# Transmitter_ks0108_version.net
KiCad netlist of a schematic drawn in EAGLE
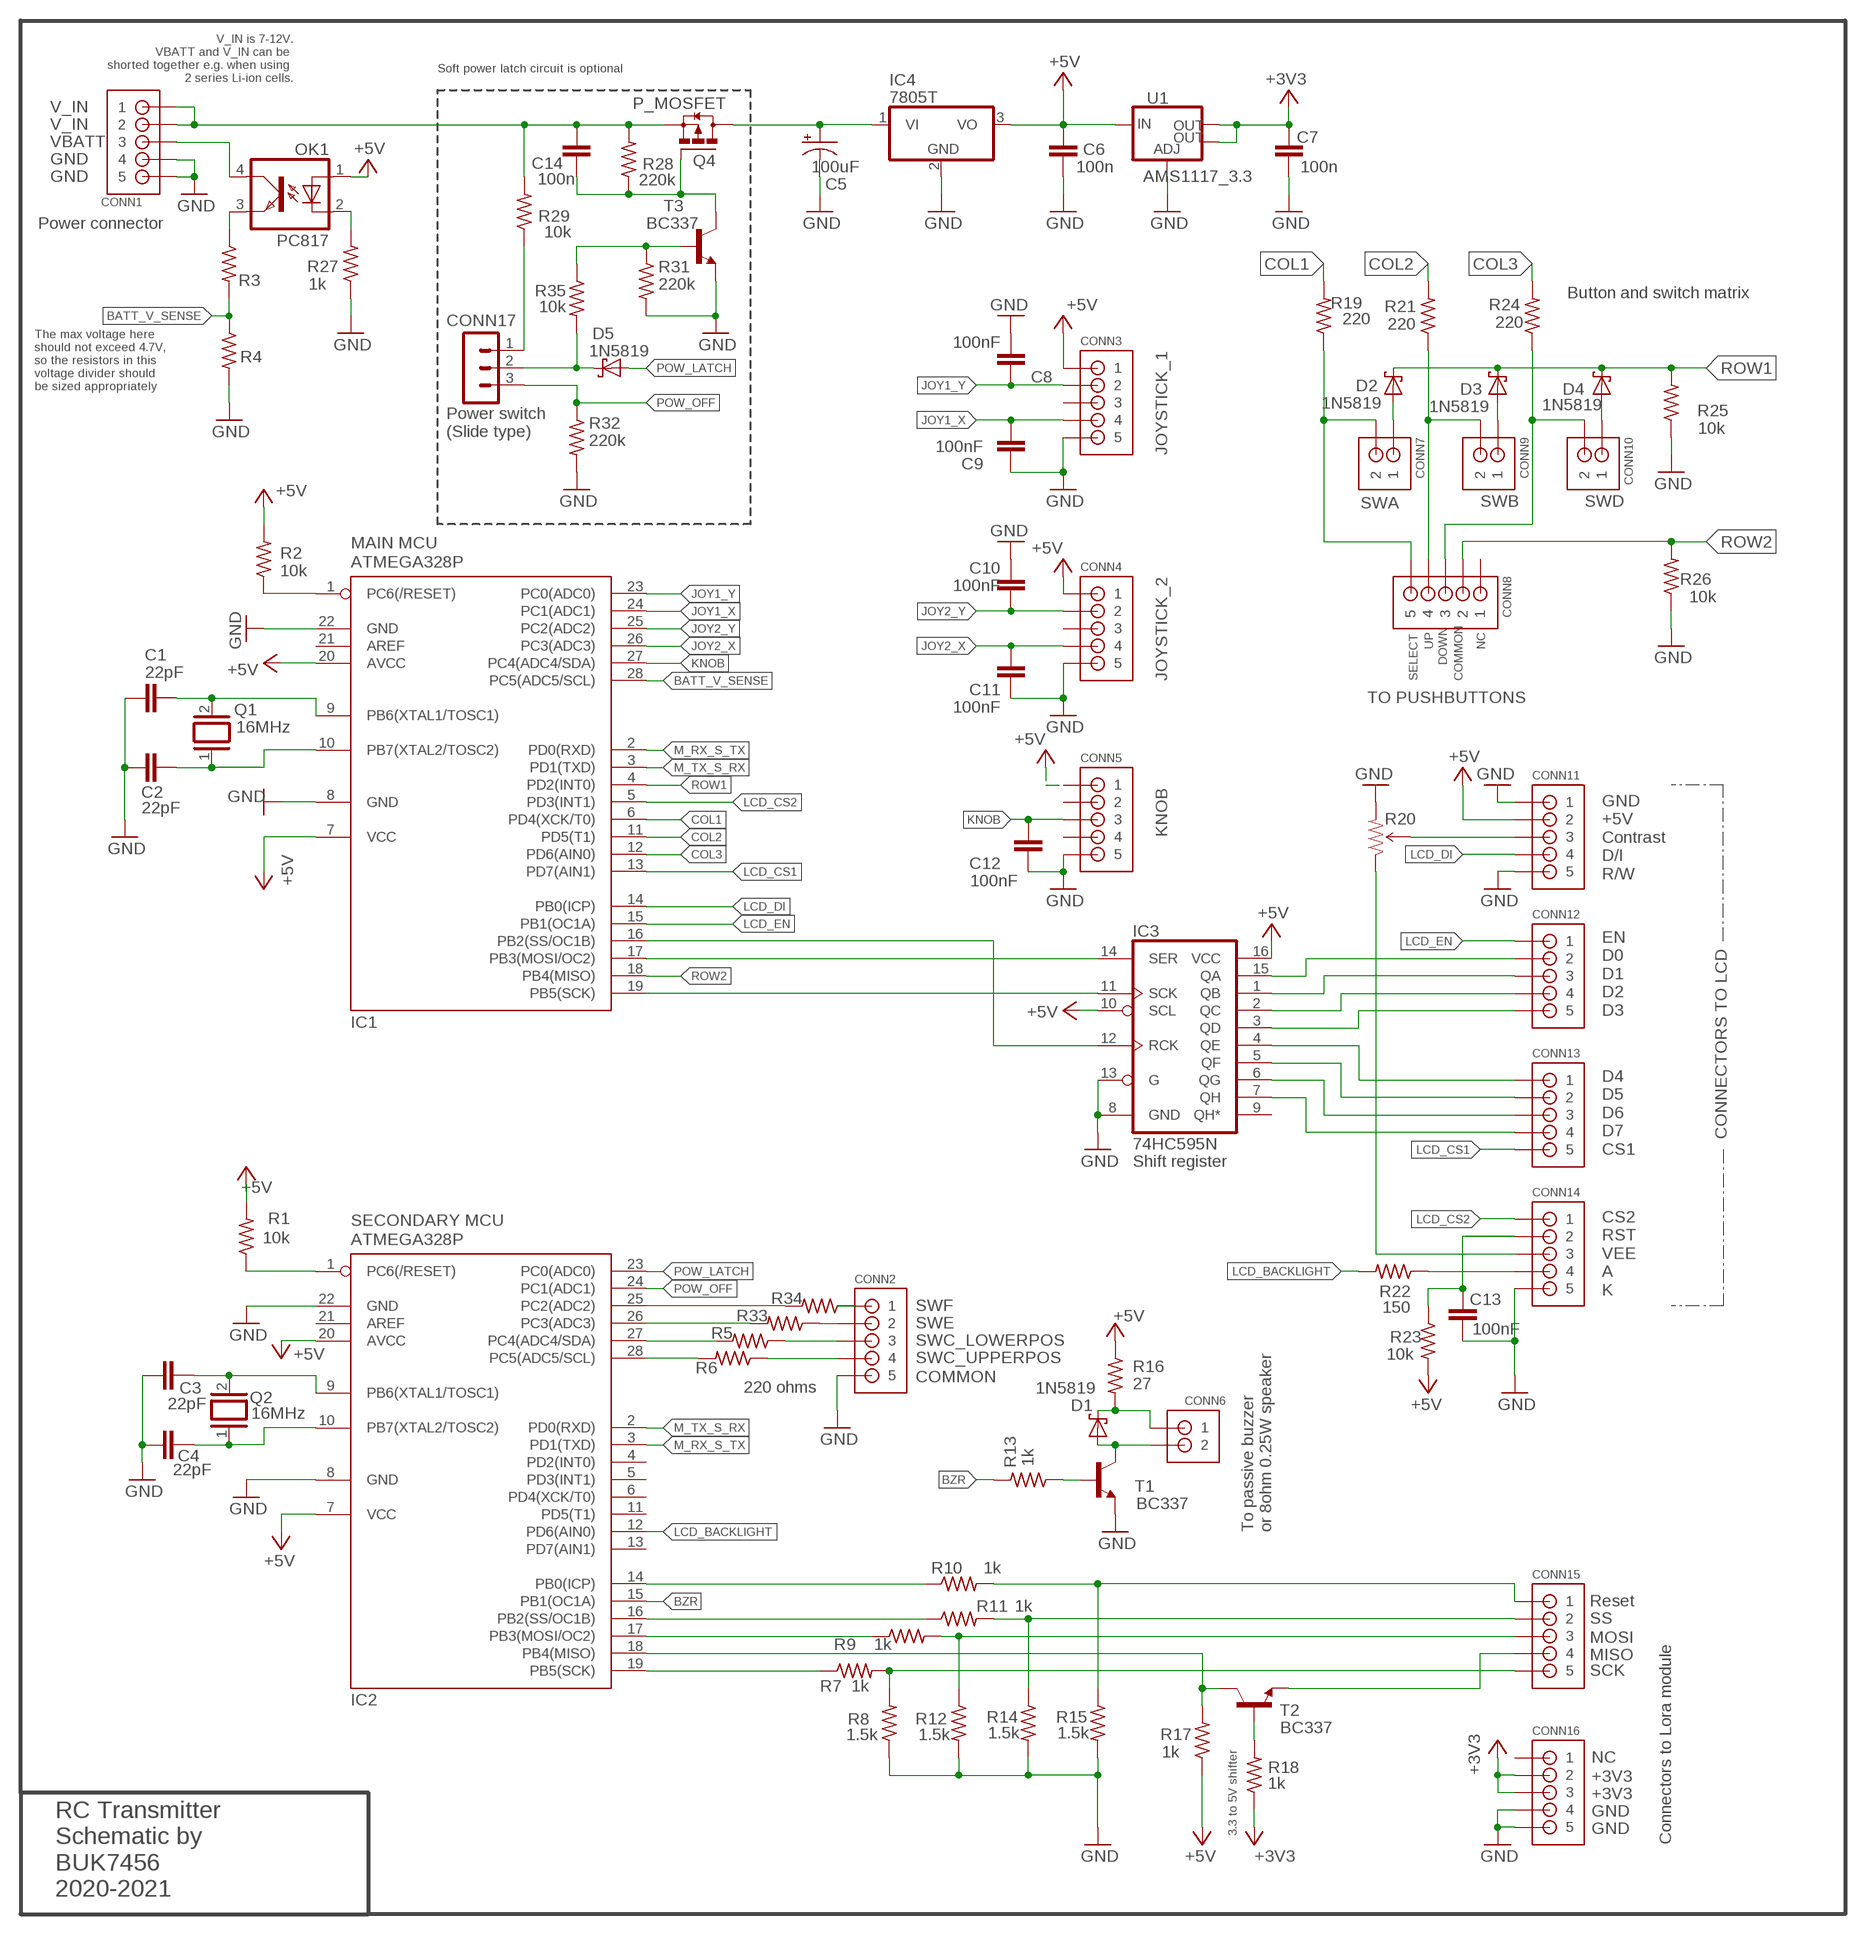
[diagram p0: schematic, sheet 1]

(export (version "E")
  (design (tool "Eeschema 10.0.6"))
  (components
    (comp (ref "C1")
      (value "22pF")
      (footprint "eagle-import:C025-025X050")
      (libsource (lib "eagle-import") (part "C-EU025-025X050"))
    )
    (comp (ref "C2")
      (value "22pF")
      (footprint "eagle-import:C025-025X050")
      (libsource (lib "eagle-import") (part "C-EU025-025X050"))
    )
    (comp (ref "C3")
      (value "22pF")
      (footprint "eagle-import:C025-025X050")
      (libsource (lib "eagle-import") (part "C-EU025-025X050"))
    )
    (comp (ref "C4")
      (value "22pF")
      (footprint "eagle-import:C025-025X050")
      (libsource (lib "eagle-import") (part "C-EU025-025X050"))
    )
    (comp (ref "C5")
      (value "100uF")
      (footprint "eagle-import:E2,5-6E")
      (libsource (lib "eagle-import") (part "CPOL-USE2,5-6E"))
    )
    (comp (ref "C6")
      (value "100n")
      (footprint "eagle-import:C025-025X050")
      (libsource (lib "eagle-import") (part "C-EU025-025X050"))
    )
    (comp (ref "C7")
      (value "100n")
      (footprint "eagle-import:C025-025X050")
      (libsource (lib "eagle-import") (part "C-EU025-025X050"))
    )
    (comp (ref "C8")
      (value "100nF")
      (footprint "eagle-import:C025-025X050")
      (libsource (lib "eagle-import") (part "C-EU025-025X050"))
    )
    (comp (ref "C9")
      (value "100nF")
      (footprint "eagle-import:C025-025X050")
      (libsource (lib "eagle-import") (part "C-EU025-025X050"))
    )
    (comp (ref "C10")
      (value "100nF")
      (footprint "eagle-import:C025-025X050")
      (libsource (lib "eagle-import") (part "C-EU025-025X050"))
    )
    (comp (ref "C11")
      (value "100nF")
      (footprint "eagle-import:C025-025X050")
      (libsource (lib "eagle-import") (part "C-EU025-025X050"))
    )
    (comp (ref "C12")
      (value "100nF")
      (footprint "eagle-import:C025-025X050")
      (libsource (lib "eagle-import") (part "C-EU025-025X050"))
    )
    (comp (ref "C13")
      (value "100nF")
      (footprint "eagle-import:C025-025X050")
      (libsource (lib "eagle-import") (part "C-EU025-025X050"))
    )
    (comp (ref "C14")
      (value "100n")
      (footprint "eagle-import:C025-025X050")
      (libsource (lib "eagle-import") (part "C-EU025-025X050"))
    )
    (comp (ref "CONN1")
      (value "POW")
      (footprint "eagle-import:JST_B5B-PH_HEADER")
      (libsource (lib "eagle-import") (part "JST-PH_5-PIN_HEADER"))
    )
    (comp (ref "CONN2")
      (value "RADIO")
      (footprint "eagle-import:JST_B5B-PH_HEADER")
      (libsource (lib "eagle-import") (part "JST-PH_5-PIN_HEADER"))
    )
    (comp (ref "CONN3")
      (value "JST-PH_5-PIN_HEADER")
      (footprint "eagle-import:JST_B5B-PH_HEADER")
      (libsource (lib "eagle-import") (part "JST-PH_5-PIN_HEADER"))
    )
    (comp (ref "CONN4")
      (value "JST-PH_5-PIN_HEADER")
      (footprint "eagle-import:JST_B5B-PH_HEADER")
      (libsource (lib "eagle-import") (part "JST-PH_5-PIN_HEADER"))
    )
    (comp (ref "CONN5")
      (value "JST-PH_5-PIN_HEADER")
      (footprint "eagle-import:JST_B5B-PH_HEADER")
      (libsource (lib "eagle-import") (part "JST-PH_5-PIN_HEADER"))
    )
    (comp (ref "CONN6")
      (value "JST-PH_2-PIN_HEADER")
      (footprint "eagle-import:JST_B2B-PH_HEADER")
      (libsource (lib "eagle-import") (part "JST-PH_2-PIN_HEADER"))
    )
    (comp (ref "CONN7")
      (value "JST-PH_2-PIN_HEADER")
      (footprint "eagle-import:JST_B2B-PH_HEADER")
      (libsource (lib "eagle-import") (part "JST-PH_2-PIN_HEADER"))
    )
    (comp (ref "CONN8")
      (value "JST-PH_5-PIN_HEADER")
      (footprint "eagle-import:JST_B5B-PH_HEADER")
      (libsource (lib "eagle-import") (part "JST-PH_5-PIN_HEADER"))
    )
    (comp (ref "CONN9")
      (value "JST-PH_2-PIN_HEADER")
      (footprint "eagle-import:JST_B2B-PH_HEADER")
      (libsource (lib "eagle-import") (part "JST-PH_2-PIN_HEADER"))
    )
    (comp (ref "CONN10")
      (value "JST-PH_2-PIN_HEADER")
      (footprint "eagle-import:JST_B2B-PH_HEADER")
      (libsource (lib "eagle-import") (part "JST-PH_2-PIN_HEADER"))
    )
    (comp (ref "CONN11")
      (value "AUX")
      (footprint "eagle-import:JST_B5B-PH_HEADER")
      (libsource (lib "eagle-import") (part "JST-PH_5-PIN_HEADER"))
    )
    (comp (ref "CONN12")
      (value "AUX")
      (footprint "eagle-import:JST_B5B-PH_HEADER")
      (libsource (lib "eagle-import") (part "JST-PH_5-PIN_HEADER"))
    )
    (comp (ref "CONN13")
      (value "AUX")
      (footprint "eagle-import:JST_B5B-PH_HEADER")
      (libsource (lib "eagle-import") (part "JST-PH_5-PIN_HEADER"))
    )
    (comp (ref "CONN14")
      (value "AUX")
      (footprint "eagle-import:JST_B5B-PH_HEADER")
      (libsource (lib "eagle-import") (part "JST-PH_5-PIN_HEADER"))
    )
    (comp (ref "CONN15")
      (value "JST-PH_5-PIN_HEADER")
      (footprint "eagle-import:JST_B5B-PH_HEADER")
      (libsource (lib "eagle-import") (part "JST-PH_5-PIN_HEADER"))
    )
    (comp (ref "CONN16")
      (value "JST-PH_5-PIN_HEADER")
      (footprint "eagle-import:JST_B5B-PH_HEADER")
      (libsource (lib "eagle-import") (part "JST-PH_5-PIN_HEADER"))
    )
    (comp (ref "CONN17")
      (value "MA03-1")
      (footprint "eagle-import:MA03-1")
      (libsource (lib "eagle-import") (part "MA03-1"))
    )
    (comp (ref "D1")
      (value "1N5819")
      (footprint "eagle-import:DO41-7.6")
      (libsource (lib "eagle-import") (part "1N5817-B"))
    )
    (comp (ref "D2")
      (value "1N5819")
      (footprint "eagle-import:DO41-7.6")
      (libsource (lib "eagle-import") (part "1N5817-B"))
    )
    (comp (ref "D3")
      (value "1N5819")
      (footprint "eagle-import:DO41-7.6")
      (libsource (lib "eagle-import") (part "1N5817-B"))
    )
    (comp (ref "D4")
      (value "1N5819")
      (footprint "eagle-import:DO41-7.6")
      (libsource (lib "eagle-import") (part "1N5817-B"))
    )
    (comp (ref "D5")
      (value "1N5819")
      (footprint "eagle-import:DO41-7.6")
      (libsource (lib "eagle-import") (part "1N5817-B"))
    )
    (comp (ref "IC1")
      (value "ATMEGA328P")
      (footprint "eagle-import:DIL28-3")
      (libsource (lib "eagle-import") (part "MEGA8-P"))
    )
    (comp (ref "IC2")
      (value "ATMEGA328P")
      (footprint "eagle-import:DIL28-3")
      (libsource (lib "eagle-import") (part "MEGA8-P"))
    )
    (comp (ref "IC3")
      (value "74HC595N")
      (footprint "eagle-import:DIL16")
      (libsource (lib "eagle-import") (part "74595NLS"))
    )
    (comp (ref "IC4")
      (value "7805T")
      (footprint "eagle-import:TO220H")
      (libsource (lib "eagle-import") (part "78T05"))
    )
    (comp (ref "OK1")
      (value "PC817")
      (footprint "eagle-import:DIL04")
      (fields (field (name "MPN") "PC817X4J000F"))
      (libsource (lib "eagle-import") (part "PC817"))
    )
    (comp (ref "Q1")
      (value "16MHz")
      (footprint "eagle-import:QS")
      (libsource (lib "eagle-import") (part "XTAL/S"))
    )
    (comp (ref "Q2")
      (value "16MHz")
      (footprint "eagle-import:QS")
      (libsource (lib "eagle-import") (part "XTAL/S"))
    )
    (comp (ref "Q4")
      (value "P_MOSFET")
      (footprint "eagle-import:SUPER-SOT3")
      (libsource (lib "eagle-import") (part "FDN360P"))
    )
    (comp (ref "R1")
      (value "10k")
      (footprint "eagle-import:0204_5")
      (libsource (lib "eagle-import") (part "R-US_0204/5"))
    )
    (comp (ref "R2")
      (value "10k")
      (footprint "eagle-import:0207_10")
      (libsource (lib "eagle-import") (part "R-US_0207/10"))
    )
    (comp (ref "R3")
      (value "1k")
      (footprint "eagle-import:0207_10")
      (libsource (lib "eagle-import") (part "R-US_0207/10"))
    )
    (comp (ref "R4")
      (value "1k")
      (footprint "eagle-import:0204V")
      (libsource (lib "eagle-import") (part "resistor_R-US_0204/2V"))
    )
    (comp (ref "R5")
      (value "220")
      (footprint "eagle-import:0204_7")
      (libsource (lib "eagle-import") (part "R-US_0204/7"))
    )
    (comp (ref "R6")
      (value "220")
      (footprint "eagle-import:0204_7")
      (libsource (lib "eagle-import") (part "R-US_0204/7"))
    )
    (comp (ref "R7")
      (value "1k")
      (footprint "eagle-import:0204_5")
      (libsource (lib "eagle-import") (part "R-US_0204/5"))
    )
    (comp (ref "R8")
      (value "1.5k")
      (footprint "eagle-import:0204V")
      (libsource (lib "eagle-import") (part "R-US_0204/2V"))
    )
    (comp (ref "R9")
      (value "1k")
      (footprint "eagle-import:0204_5")
      (libsource (lib "eagle-import") (part "R-US_0204/5"))
    )
    (comp (ref "R10")
      (value "1k")
      (footprint "eagle-import:0204_5")
      (libsource (lib "eagle-import") (part "R-US_0204/5"))
    )
    (comp (ref "R11")
      (value "1k")
      (footprint "eagle-import:0204_5")
      (libsource (lib "eagle-import") (part "R-US_0204/5"))
    )
    (comp (ref "R12")
      (value "1.5k")
      (footprint "eagle-import:0204V")
      (libsource (lib "eagle-import") (part "R-US_0204/2V"))
    )
    (comp (ref "R13")
      (value "1k")
      (footprint "eagle-import:0204_5")
      (libsource (lib "eagle-import") (part "R-US_0204/5"))
    )
    (comp (ref "R14")
      (value "1.5k")
      (footprint "eagle-import:0204V")
      (libsource (lib "eagle-import") (part "R-US_0204/2V"))
    )
    (comp (ref "R15")
      (value "1.5k")
      (footprint "eagle-import:0204V")
      (libsource (lib "eagle-import") (part "R-US_0204/2V"))
    )
    (comp (ref "R16")
      (value "27")
      (footprint "eagle-import:0204_7")
      (libsource (lib "eagle-import") (part "R-US_0204/7"))
    )
    (comp (ref "R17")
      (value "1k")
      (footprint "eagle-import:0204_7")
      (libsource (lib "eagle-import") (part "R-US_0204/7"))
    )
    (comp (ref "R18")
      (value "1k")
      (footprint "eagle-import:0204_5")
      (libsource (lib "eagle-import") (part "R-US_0204/5"))
    )
    (comp (ref "R19")
      (value "220")
      (footprint "eagle-import:0204_7")
      (libsource (lib "eagle-import") (part "R-US_0204/7"))
    )
    (comp (ref "R20")
      (value "TRIMPOTPTH")
      (footprint "eagle-import:TRIM_POT_PTH")
      (libsource (lib "eagle-import") (part "TRIMPOTPTH"))
    )
    (comp (ref "R21")
      (value "220")
      (footprint "eagle-import:0207_10")
      (libsource (lib "eagle-import") (part "R-US_0207/10"))
    )
    (comp (ref "R22")
      (value "150")
      (footprint "eagle-import:0204V")
      (libsource (lib "eagle-import") (part "R-US_0204/2V"))
    )
    (comp (ref "R23")
      (value "10k")
      (footprint "eagle-import:0204_5")
      (libsource (lib "eagle-import") (part "resistor_R-US_0204/5"))
    )
    (comp (ref "R24")
      (value "220")
      (footprint "eagle-import:0204_7")
      (libsource (lib "eagle-import") (part "R-US_0204/7"))
    )
    (comp (ref "R25")
      (value "10k")
      (footprint "eagle-import:0204V")
      (libsource (lib "eagle-import") (part "R-US_0204/2V"))
    )
    (comp (ref "R26")
      (value "10k")
      (footprint "eagle-import:0204V")
      (libsource (lib "eagle-import") (part "R-US_0204/2V"))
    )
    (comp (ref "R27")
      (value "1k")
      (footprint "eagle-import:0204V")
      (libsource (lib "eagle-import") (part "R-US_0204/2V"))
    )
    (comp (ref "R28")
      (value "220k")
      (footprint "eagle-import:0204_7")
      (libsource (lib "eagle-import") (part "R-US_0204/7"))
    )
    (comp (ref "R29")
      (value "10k")
      (footprint "eagle-import:0204_7")
      (libsource (lib "eagle-import") (part "R-US_0204/7"))
    )
    (comp (ref "R31")
      (value "220k")
      (footprint "eagle-import:0204_7")
      (libsource (lib "eagle-import") (part "R-US_0204/7"))
    )
    (comp (ref "R32")
      (value "220k")
      (footprint "eagle-import:0204_7")
      (libsource (lib "eagle-import") (part "R-US_0204/7"))
    )
    (comp (ref "R33")
      (value "220")
      (footprint "eagle-import:0204_7")
      (libsource (lib "eagle-import") (part "R-US_0204/7"))
    )
    (comp (ref "R34")
      (value "220")
      (footprint "eagle-import:0204_7")
      (libsource (lib "eagle-import") (part "R-US_0204/7"))
    )
    (comp (ref "R35")
      (value "10k")
      (footprint "eagle-import:0204_7")
      (libsource (lib "eagle-import") (part "R-US_0204/7"))
    )
    (comp (ref "T1")
      (value "BC337")
      (footprint "eagle-import:TO92")
      (libsource (lib "eagle-import") (part "BC337"))
    )
    (comp (ref "T2")
      (value "BC337")
      (footprint "eagle-import:TO92")
      (libsource (lib "eagle-import") (part "BC337"))
    )
    (comp (ref "T3")
      (value "BC337")
      (footprint "eagle-import:TO92")
      (libsource (lib "eagle-import") (part "BC337"))
    )
    (comp (ref "U1")
      (value "AMS1117_3.3")
      (footprint "eagle-import:SOT223")
      (libsource (lib "eagle-import") (part "V_REG_LM1117SOT223"))
    )
  )
  (nets
    (net (code "1") (name "+3V3") (class "Default")
      (node (ref "C7") (pin "2") (pinfunction "2_2") (pintype "passive"))
      (node (ref "CONN16") (pin "P2") (pinfunction "2_P2") (pintype "bidirectional"))
      (node (ref "CONN16") (pin "P3") (pinfunction "3_P3") (pintype "bidirectional"))
      (node (ref "R18") (pin "1") (pinfunction "1_1") (pintype "passive"))
      (node (ref "U1") (pin "2") (pinfunction "OUT_2") (pintype "output"))
      (node (ref "U1") (pin "4") (pinfunction "OUT_4") (pintype "output"))
    )
    (net (code "2") (name "+5V") (class "Default")
      (node (ref "C6") (pin "2") (pinfunction "2_2") (pintype "passive"))
      (node (ref "CONN11") (pin "P2") (pinfunction "2_P2") (pintype "bidirectional"))
      (node (ref "CONN3") (pin "P1") (pinfunction "1_P1") (pintype "bidirectional"))
      (node (ref "CONN4") (pin "P1") (pinfunction "1_P1") (pintype "bidirectional"))
      (node (ref "CONN5") (pin "P1") (pinfunction "1_P1") (pintype "bidirectional"))
      (node (ref "IC1") (pin "20") (pinfunction "AVCC_20") (pintype "power_in"))
      (node (ref "IC1") (pin "7") (pinfunction "VCC_7") (pintype "power_in"))
      (node (ref "IC2") (pin "20") (pinfunction "AVCC_20") (pintype "power_in"))
      (node (ref "IC2") (pin "7") (pinfunction "VCC_7") (pintype "power_in"))
      (node (ref "IC3") (pin "10") (pinfunction "SCL_10") (pintype "input"))
      (node (ref "IC3") (pin "16") (pinfunction "VCC_16") (pintype "power_in"))
      (node (ref "IC4") (pin "3") (pinfunction "VO_3") (pintype "passive"))
      (node (ref "OK1") (pin "1") (pinfunction "A_1") (pintype "passive"))
      (node (ref "R1") (pin "2") (pinfunction "2_2") (pintype "passive"))
      (node (ref "R16") (pin "1") (pinfunction "1_1") (pintype "passive"))
      (node (ref "R17") (pin "1") (pinfunction "1_1") (pintype "passive"))
      (node (ref "R2") (pin "2") (pinfunction "2_2") (pintype "passive"))
      (node (ref "R23") (pin "2") (pinfunction "2_2") (pintype "passive"))
      (node (ref "U1") (pin "3") (pinfunction "IN_3") (pintype "input"))
    )
    (net (code "3") (name "BATT_V_SENSE") (class "Default")
      (node (ref "IC1") (pin "28") (pinfunction "PC5(ADC5/SCL)_28") (pintype "bidirectional"))
      (node (ref "R3") (pin "2") (pinfunction "2_2") (pintype "passive"))
      (node (ref "R4") (pin "1") (pinfunction "1_1") (pintype "passive"))
    )
    (net (code "4") (name "BZR") (class "Default")
      (node (ref "IC2") (pin "15") (pinfunction "PB1(OC1A)_15") (pintype "bidirectional"))
      (node (ref "R13") (pin "2") (pinfunction "2_2") (pintype "passive"))
    )
    (net (code "5") (name "COL1") (class "Default")
      (node (ref "IC1") (pin "6") (pinfunction "PD4(XCK/T0)_6") (pintype "bidirectional"))
      (node (ref "R19") (pin "2") (pinfunction "2_2") (pintype "passive"))
    )
    (net (code "6") (name "COL2") (class "Default")
      (node (ref "IC1") (pin "11") (pinfunction "PD5(T1)_11") (pintype "bidirectional"))
      (node (ref "R21") (pin "2") (pinfunction "2_2") (pintype "passive"))
    )
    (net (code "7") (name "COL3") (class "Default")
      (node (ref "IC1") (pin "12") (pinfunction "PD6(AIN0)_12") (pintype "bidirectional"))
      (node (ref "R24") (pin "2") (pinfunction "2_2") (pintype "passive"))
    )
    (net (code "8") (name "GND") (class "Default")
      (node (ref "C1") (pin "1") (pinfunction "1_1") (pintype "passive"))
      (node (ref "C10") (pin "2") (pinfunction "2_2") (pintype "passive"))
      (node (ref "C11") (pin "1") (pinfunction "1_1") (pintype "passive"))
      (node (ref "C12") (pin "1") (pinfunction "1_1") (pintype "passive"))
      (node (ref "C13") (pin "2") (pinfunction "2_2") (pintype "passive"))
      (node (ref "C2") (pin "1") (pinfunction "1_1") (pintype "passive"))
      (node (ref "C3") (pin "1") (pinfunction "1_1") (pintype "passive"))
      (node (ref "C4") (pin "1") (pinfunction "1_1") (pintype "passive"))
      (node (ref "C5") (pin "-") (pinfunction "-_-") (pintype "passive"))
      (node (ref "C6") (pin "1") (pinfunction "1_1") (pintype "passive"))
      (node (ref "C7") (pin "1") (pinfunction "1_1") (pintype "passive"))
      (node (ref "C8") (pin "2") (pinfunction "2_2") (pintype "passive"))
      (node (ref "C9") (pin "1") (pinfunction "1_1") (pintype "passive"))
      (node (ref "CONN1") (pin "P4") (pinfunction "4_P4") (pintype "bidirectional"))
      (node (ref "CONN1") (pin "P5") (pinfunction "5_P5") (pintype "bidirectional"))
      (node (ref "CONN11") (pin "P1") (pinfunction "1_P1") (pintype "bidirectional"))
      (node (ref "CONN11") (pin "P5") (pinfunction "5_P5") (pintype "bidirectional"))
      (node (ref "CONN14") (pin "P5") (pinfunction "5_P5") (pintype "bidirectional"))
      (node (ref "CONN16") (pin "P4") (pinfunction "4_P4") (pintype "bidirectional"))
      (node (ref "CONN16") (pin "P5") (pinfunction "5_P5") (pintype "bidirectional"))
      (node (ref "CONN2") (pin "P5") (pinfunction "5_P5") (pintype "bidirectional"))
      (node (ref "CONN3") (pin "P5") (pinfunction "5_P5") (pintype "bidirectional"))
      (node (ref "CONN4") (pin "P5") (pinfunction "5_P5") (pintype "bidirectional"))
      (node (ref "CONN5") (pin "P5") (pinfunction "5_P5") (pintype "bidirectional"))
      (node (ref "IC1") (pin "22") (pinfunction "GND_22") (pintype "power_in"))
      (node (ref "IC1") (pin "8") (pinfunction "GND_8") (pintype "power_in"))
      (node (ref "IC2") (pin "22") (pinfunction "GND_22") (pintype "power_in"))
      (node (ref "IC2") (pin "8") (pinfunction "GND_8") (pintype "power_in"))
      (node (ref "IC3") (pin "13") (pinfunction "G_13") (pintype "input"))
      (node (ref "IC3") (pin "8") (pinfunction "GND_8") (pintype "power_in"))
      (node (ref "IC4") (pin "2") (pinfunction "GND_2") (pintype "passive"))
      (node (ref "R12") (pin "2") (pinfunction "2_2") (pintype "passive"))
      (node (ref "R14") (pin "2") (pinfunction "2_2") (pintype "passive"))
      (node (ref "R15") (pin "2") (pinfunction "2_2") (pintype "passive"))
      (node (ref "R20") (pin "3") (pinfunction "CW_3") (pintype "passive"))
      (node (ref "R25") (pin "1") (pinfunction "1_1") (pintype "passive"))
      (node (ref "R26") (pin "1") (pinfunction "1_1") (pintype "passive"))
      (node (ref "R27") (pin "1") (pinfunction "1_1") (pintype "passive"))
      (node (ref "R31") (pin "2") (pinfunction "2_2") (pintype "passive"))
      (node (ref "R32") (pin "2") (pinfunction "2_2") (pintype "passive"))
      (node (ref "R4") (pin "2") (pinfunction "2_2") (pintype "passive"))
      (node (ref "R8") (pin "1") (pinfunction "1_1") (pintype "passive"))
      (node (ref "T1") (pin "1") (pinfunction "E_1") (pintype "passive"))
      (node (ref "T3") (pin "1") (pinfunction "E_1") (pintype "passive"))
      (node (ref "U1") (pin "1") (pinfunction "ADJ_1") (pintype "input"))
    )
    (net (code "9") (name "JOY1_X") (class "Default")
      (node (ref "C9") (pin "2") (pinfunction "2_2") (pintype "passive"))
      (node (ref "CONN3") (pin "P4") (pinfunction "4_P4") (pintype "bidirectional"))
      (node (ref "IC1") (pin "24") (pinfunction "PC1(ADC1)_24") (pintype "bidirectional"))
    )
    (net (code "10") (name "JOY1_Y") (class "Default")
      (node (ref "C8") (pin "1") (pinfunction "1_1") (pintype "passive"))
      (node (ref "CONN3") (pin "P2") (pinfunction "2_P2") (pintype "bidirectional"))
      (node (ref "IC1") (pin "23") (pinfunction "PC0(ADC0)_23") (pintype "bidirectional"))
    )
    (net (code "11") (name "JOY2_X") (class "Default")
      (node (ref "C11") (pin "2") (pinfunction "2_2") (pintype "passive"))
      (node (ref "CONN4") (pin "P4") (pinfunction "4_P4") (pintype "bidirectional"))
      (node (ref "IC1") (pin "26") (pinfunction "PC3(ADC3)_26") (pintype "bidirectional"))
    )
    (net (code "12") (name "JOY2_Y") (class "Default")
      (node (ref "C10") (pin "1") (pinfunction "1_1") (pintype "passive"))
      (node (ref "CONN4") (pin "P2") (pinfunction "2_P2") (pintype "bidirectional"))
      (node (ref "IC1") (pin "25") (pinfunction "PC2(ADC2)_25") (pintype "bidirectional"))
    )
    (net (code "13") (name "KNOB") (class "Default")
      (node (ref "C12") (pin "2") (pinfunction "2_2") (pintype "passive"))
      (node (ref "CONN5") (pin "P3") (pinfunction "3_P3") (pintype "bidirectional"))
      (node (ref "IC1") (pin "27") (pinfunction "PC4(ADC4/SDA)_27") (pintype "bidirectional"))
    )
    (net (code "14") (name "LCD_BACKLIGHT") (class "Default")
      (node (ref "IC2") (pin "12") (pinfunction "PD6(AIN0)_12") (pintype "bidirectional"))
      (node (ref "R22") (pin "2") (pinfunction "2_2") (pintype "passive"))
    )
    (net (code "15") (name "LCD_CS1") (class "Default")
      (node (ref "CONN13") (pin "P5") (pinfunction "5_P5") (pintype "bidirectional"))
      (node (ref "IC1") (pin "13") (pinfunction "PD7(AIN1)_13") (pintype "bidirectional"))
    )
    (net (code "16") (name "LCD_CS2") (class "Default")
      (node (ref "CONN14") (pin "P1") (pinfunction "1_P1") (pintype "bidirectional"))
      (node (ref "IC1") (pin "5") (pinfunction "PD3(INT1)_5") (pintype "bidirectional"))
    )
    (net (code "17") (name "LCD_DI") (class "Default")
      (node (ref "CONN11") (pin "P4") (pinfunction "4_P4") (pintype "bidirectional"))
      (node (ref "IC1") (pin "14") (pinfunction "PB0(ICP)_14") (pintype "bidirectional"))
    )
    (net (code "18") (name "LCD_EN") (class "Default")
      (node (ref "CONN12") (pin "P1") (pinfunction "1_P1") (pintype "bidirectional"))
      (node (ref "IC1") (pin "15") (pinfunction "PB1(OC1A)_15") (pintype "bidirectional"))
    )
    (net (code "19") (name "M_RX_S_TX") (class "Default")
      (node (ref "IC1") (pin "2") (pinfunction "PD0(RXD)_2") (pintype "bidirectional"))
      (node (ref "IC2") (pin "3") (pinfunction "PD1(TXD)_3") (pintype "bidirectional"))
    )
    (net (code "20") (name "M_TX_S_RX") (class "Default")
      (node (ref "IC1") (pin "3") (pinfunction "PD1(TXD)_3") (pintype "bidirectional"))
      (node (ref "IC2") (pin "2") (pinfunction "PD0(RXD)_2") (pintype "bidirectional"))
    )
    (net (code "21") (name "Net-(CONN1-1)") (class "Default")
      (node (ref "C14") (pin "2") (pinfunction "2_2") (pintype "passive"))
      (node (ref "CONN1") (pin "P1") (pinfunction "1_P1") (pintype "bidirectional"))
      (node (ref "CONN1") (pin "P2") (pinfunction "2_P2") (pintype "bidirectional"))
      (node (ref "Q4") (pin "2") (pinfunction "S_2") (pintype "passive"))
      (node (ref "R28") (pin "2") (pinfunction "2_2") (pintype "passive"))
      (node (ref "R29") (pin "2") (pinfunction "2_2") (pintype "passive"))
    )
    (net (code "22") (name "Net-(CONN1-3)") (class "Default")
      (node (ref "CONN1") (pin "P3") (pinfunction "3_P3") (pintype "bidirectional"))
      (node (ref "OK1") (pin "4") (pinfunction "COL_4") (pintype "passive"))
    )
    (net (code "23") (name "Net-(CONN2-1)") (class "Default")
      (node (ref "CONN2") (pin "P1") (pinfunction "1_P1") (pintype "bidirectional"))
      (node (ref "R34") (pin "1") (pinfunction "1_1") (pintype "passive"))
    )
    (net (code "24") (name "Net-(CONN2-2)") (class "Default")
      (node (ref "CONN2") (pin "P2") (pinfunction "2_P2") (pintype "bidirectional"))
      (node (ref "R33") (pin "1") (pinfunction "1_1") (pintype "passive"))
    )
    (net (code "25") (name "Net-(CONN2-3)") (class "Default")
      (node (ref "CONN2") (pin "P3") (pinfunction "3_P3") (pintype "bidirectional"))
      (node (ref "R5") (pin "1") (pinfunction "1_1") (pintype "passive"))
    )
    (net (code "26") (name "Net-(CONN2-4)") (class "Default")
      (node (ref "CONN2") (pin "P4") (pinfunction "4_P4") (pintype "bidirectional"))
      (node (ref "R6") (pin "1") (pinfunction "1_1") (pintype "passive"))
    )
    (net (code "27") (name "Net-(CONN6-1)") (class "Default")
      (node (ref "CONN6") (pin "P1") (pinfunction "1_P1") (pintype "bidirectional"))
      (node (ref "D1") (pin "C") (pinfunction "C_C") (pintype "passive"))
      (node (ref "R16") (pin "2") (pinfunction "2_2") (pintype "passive"))
    )
    (net (code "28") (name "Net-(CONN6-2)") (class "Default")
      (node (ref "CONN6") (pin "P2") (pinfunction "2_P2") (pintype "bidirectional"))
      (node (ref "D1") (pin "A") (pinfunction "A_A") (pintype "passive"))
      (node (ref "T1") (pin "3") (pinfunction "C_3") (pintype "passive"))
    )
    (net (code "29") (name "Net-(CONN7-1)") (class "Default")
      (node (ref "CONN7") (pin "P1") (pinfunction "1_P1") (pintype "bidirectional"))
      (node (ref "D2") (pin "A") (pinfunction "A_A") (pintype "passive"))
    )
    (net (code "30") (name "Net-(CONN7-2)") (class "Default")
      (node (ref "CONN7") (pin "P2") (pinfunction "2_P2") (pintype "bidirectional"))
      (node (ref "CONN8") (pin "P5") (pinfunction "5_P5") (pintype "bidirectional"))
      (node (ref "R19") (pin "1") (pinfunction "1_1") (pintype "passive"))
    )
    (net (code "31") (name "Net-(CONN8-4)") (class "Default")
      (node (ref "CONN8") (pin "P4") (pinfunction "4_P4") (pintype "bidirectional"))
      (node (ref "CONN9") (pin "P2") (pinfunction "2_P2") (pintype "bidirectional"))
      (node (ref "R21") (pin "1") (pinfunction "1_1") (pintype "passive"))
    )
    (net (code "32") (name "Net-(CONN9-1)") (class "Default")
      (node (ref "CONN9") (pin "P1") (pinfunction "1_P1") (pintype "bidirectional"))
      (node (ref "D3") (pin "A") (pinfunction "A_A") (pintype "passive"))
    )
    (net (code "33") (name "Net-(CONN10-1)") (class "Default")
      (node (ref "CONN10") (pin "P1") (pinfunction "1_P1") (pintype "bidirectional"))
      (node (ref "D4") (pin "A") (pinfunction "A_A") (pintype "passive"))
    )
    (net (code "34") (name "Net-(CONN10-2)") (class "Default")
      (node (ref "CONN10") (pin "P2") (pinfunction "2_P2") (pintype "bidirectional"))
      (node (ref "CONN8") (pin "P3") (pinfunction "3_P3") (pintype "bidirectional"))
      (node (ref "R24") (pin "1") (pinfunction "1_1") (pintype "passive"))
    )
    (net (code "35") (name "Net-(CONN11-3)") (class "Default")
      (node (ref "CONN11") (pin "P3") (pinfunction "3_P3") (pintype "bidirectional"))
      (node (ref "R20") (pin "2") (pinfunction "WIPER_2") (pintype "passive"))
    )
    (net (code "36") (name "Net-(CONN12-2)") (class "Default")
      (node (ref "CONN12") (pin "P2") (pinfunction "2_P2") (pintype "bidirectional"))
      (node (ref "IC3") (pin "15") (pinfunction "QA_15") (pintype "tri_state"))
    )
    (net (code "37") (name "Net-(CONN12-3)") (class "Default")
      (node (ref "CONN12") (pin "P3") (pinfunction "3_P3") (pintype "bidirectional"))
      (node (ref "IC3") (pin "1") (pinfunction "QB_1") (pintype "tri_state"))
    )
    (net (code "38") (name "Net-(CONN12-4)") (class "Default")
      (node (ref "CONN12") (pin "P4") (pinfunction "4_P4") (pintype "bidirectional"))
      (node (ref "IC3") (pin "2") (pinfunction "QC_2") (pintype "tri_state"))
    )
    (net (code "39") (name "Net-(CONN12-5)") (class "Default")
      (node (ref "CONN12") (pin "P5") (pinfunction "5_P5") (pintype "bidirectional"))
      (node (ref "IC3") (pin "3") (pinfunction "QD_3") (pintype "tri_state"))
    )
    (net (code "40") (name "Net-(CONN13-1)") (class "Default")
      (node (ref "CONN13") (pin "P1") (pinfunction "1_P1") (pintype "bidirectional"))
      (node (ref "IC3") (pin "4") (pinfunction "QE_4") (pintype "tri_state"))
    )
    (net (code "41") (name "Net-(CONN13-2)") (class "Default")
      (node (ref "CONN13") (pin "P2") (pinfunction "2_P2") (pintype "bidirectional"))
      (node (ref "IC3") (pin "5") (pinfunction "QF_5") (pintype "tri_state"))
    )
    (net (code "42") (name "Net-(CONN13-3)") (class "Default")
      (node (ref "CONN13") (pin "P3") (pinfunction "3_P3") (pintype "bidirectional"))
      (node (ref "IC3") (pin "6") (pinfunction "QG_6") (pintype "tri_state"))
    )
    (net (code "43") (name "Net-(CONN13-4)") (class "Default")
      (node (ref "CONN13") (pin "P4") (pinfunction "4_P4") (pintype "bidirectional"))
      (node (ref "IC3") (pin "7") (pinfunction "QH_7") (pintype "tri_state"))
    )
    (net (code "44") (name "Net-(CONN14-2)") (class "Default")
      (node (ref "C13") (pin "1") (pinfunction "1_1") (pintype "passive"))
      (node (ref "CONN14") (pin "P2") (pinfunction "2_P2") (pintype "bidirectional"))
      (node (ref "R23") (pin "1") (pinfunction "1_1") (pintype "passive"))
    )
    (net (code "45") (name "Net-(CONN14-3)") (class "Default")
      (node (ref "CONN14") (pin "P3") (pinfunction "3_P3") (pintype "bidirectional"))
      (node (ref "R20") (pin "1") (pinfunction "CCW_1") (pintype "passive"))
    )
    (net (code "46") (name "Net-(CONN14-4)") (class "Default")
      (node (ref "CONN14") (pin "P4") (pinfunction "4_P4") (pintype "bidirectional"))
      (node (ref "R22") (pin "1") (pinfunction "1_1") (pintype "passive"))
    )
    (net (code "47") (name "Net-(CONN15-1)") (class "Default")
      (node (ref "CONN15") (pin "P1") (pinfunction "1_P1") (pintype "bidirectional"))
      (node (ref "R10") (pin "2") (pinfunction "2_2") (pintype "passive"))
      (node (ref "R15") (pin "1") (pinfunction "1_1") (pintype "passive"))
    )
    (net (code "48") (name "Net-(CONN15-2)") (class "Default")
      (node (ref "CONN15") (pin "P2") (pinfunction "2_P2") (pintype "bidirectional"))
      (node (ref "R11") (pin "2") (pinfunction "2_2") (pintype "passive"))
      (node (ref "R14") (pin "1") (pinfunction "1_1") (pintype "passive"))
    )
    (net (code "49") (name "Net-(CONN15-3)") (class "Default")
      (node (ref "CONN15") (pin "P3") (pinfunction "3_P3") (pintype "bidirectional"))
      (node (ref "R12") (pin "1") (pinfunction "1_1") (pintype "passive"))
      (node (ref "R9") (pin "2") (pinfunction "2_2") (pintype "passive"))
    )
    (net (code "50") (name "Net-(CONN15-4)") (class "Default")
      (node (ref "CONN15") (pin "P4") (pinfunction "4_P4") (pintype "bidirectional"))
      (node (ref "T2") (pin "1") (pinfunction "E_1") (pintype "passive"))
    )
    (net (code "51") (name "Net-(CONN15-5)") (class "Default")
      (node (ref "CONN15") (pin "P5") (pinfunction "5_P5") (pintype "bidirectional"))
      (node (ref "R7") (pin "2") (pinfunction "2_2") (pintype "passive"))
      (node (ref "R8") (pin "2") (pinfunction "2_2") (pintype "passive"))
    )
    (net (code "52") (name "Net-(CONN17-Pad1)") (class "Default")
      (node (ref "CONN17") (pin "1") (pinfunction "1_1") (pintype "passive"))
      (node (ref "R29") (pin "1") (pinfunction "1_1") (pintype "passive"))
    )
    (net (code "53") (name "Net-(CONN17-Pad2)") (class "Default")
      (node (ref "CONN17") (pin "2") (pinfunction "2_2") (pintype "passive"))
      (node (ref "D5") (pin "C") (pinfunction "C_C") (pintype "passive"))
      (node (ref "R35") (pin "2") (pinfunction "2_2") (pintype "passive"))
    )
    (net (code "54") (name "Net-(IC1-PB2(SS{slash}OC1B))") (class "Default")
      (node (ref "IC1") (pin "16") (pinfunction "PB2(SS/OC1B)_16") (pintype "bidirectional"))
      (node (ref "IC3") (pin "12") (pinfunction "RCK_12") (pintype "input"))
    )
    (net (code "55") (name "Net-(IC1-PB3(MOSI{slash}OC2))") (class "Default")
      (node (ref "IC1") (pin "17") (pinfunction "PB3(MOSI/OC2)_17") (pintype "bidirectional"))
      (node (ref "IC3") (pin "14") (pinfunction "SER_14") (pintype "input"))
    )
    (net (code "56") (name "Net-(IC1-PB5(SCK))") (class "Default")
      (node (ref "IC1") (pin "19") (pinfunction "PB5(SCK)_19") (pintype "bidirectional"))
      (node (ref "IC3") (pin "11") (pinfunction "SCK_11") (pintype "input"))
    )
    (net (code "57") (name "Net-(IC1-PB6(XTAL1{slash}TOSC1))") (class "Default")
      (node (ref "C1") (pin "2") (pinfunction "2_2") (pintype "passive"))
      (node (ref "IC1") (pin "9") (pinfunction "PB6(XTAL1/TOSC1)_9") (pintype "bidirectional"))
      (node (ref "Q1") (pin "2") (pinfunction "2_2") (pintype "passive"))
    )
    (net (code "58") (name "Net-(IC1-PB7(XTAL2{slash}TOSC2))") (class "Default")
      (node (ref "C2") (pin "2") (pinfunction "2_2") (pintype "passive"))
      (node (ref "IC1") (pin "10") (pinfunction "PB7(XTAL2/TOSC2)_10") (pintype "bidirectional"))
      (node (ref "Q1") (pin "1") (pinfunction "1_1") (pintype "passive"))
    )
    (net (code "59") (name "Net-(IC1-PC6({slash}RESET))") (class "Default")
      (node (ref "IC1") (pin "1") (pinfunction "PC6(/RESET)_1") (pintype "bidirectional"))
      (node (ref "R2") (pin "1") (pinfunction "1_1") (pintype "passive"))
    )
    (net (code "60") (name "Net-(IC2-PB0(ICP))") (class "Default")
      (node (ref "IC2") (pin "14") (pinfunction "PB0(ICP)_14") (pintype "bidirectional"))
      (node (ref "R10") (pin "1") (pinfunction "1_1") (pintype "passive"))
    )
    (net (code "61") (name "Net-(IC2-PB2(SS{slash}OC1B))") (class "Default")
      (node (ref "IC2") (pin "16") (pinfunction "PB2(SS/OC1B)_16") (pintype "bidirectional"))
      (node (ref "R11") (pin "1") (pinfunction "1_1") (pintype "passive"))
    )
    (net (code "62") (name "Net-(IC2-PB3(MOSI{slash}OC2))") (class "Default")
      (node (ref "IC2") (pin "17") (pinfunction "PB3(MOSI/OC2)_17") (pintype "bidirectional"))
      (node (ref "R9") (pin "1") (pinfunction "1_1") (pintype "passive"))
    )
    (net (code "63") (name "Net-(IC2-PB4(MISO))") (class "Default")
      (node (ref "IC2") (pin "18") (pinfunction "PB4(MISO)_18") (pintype "bidirectional"))
      (node (ref "R17") (pin "2") (pinfunction "2_2") (pintype "passive"))
      (node (ref "T2") (pin "3") (pinfunction "C_3") (pintype "passive"))
    )
    (net (code "64") (name "Net-(IC2-PB5(SCK))") (class "Default")
      (node (ref "IC2") (pin "19") (pinfunction "PB5(SCK)_19") (pintype "bidirectional"))
      (node (ref "R7") (pin "1") (pinfunction "1_1") (pintype "passive"))
    )
    (net (code "65") (name "Net-(IC2-PB6(XTAL1{slash}TOSC1))") (class "Default")
      (node (ref "C3") (pin "2") (pinfunction "2_2") (pintype "passive"))
      (node (ref "IC2") (pin "9") (pinfunction "PB6(XTAL1/TOSC1)_9") (pintype "bidirectional"))
      (node (ref "Q2") (pin "2") (pinfunction "2_2") (pintype "passive"))
    )
    (net (code "66") (name "Net-(IC2-PB7(XTAL2{slash}TOSC2))") (class "Default")
      (node (ref "C4") (pin "2") (pinfunction "2_2") (pintype "passive"))
      (node (ref "IC2") (pin "10") (pinfunction "PB7(XTAL2/TOSC2)_10") (pintype "bidirectional"))
      (node (ref "Q2") (pin "1") (pinfunction "1_1") (pintype "passive"))
    )
    (net (code "67") (name "Net-(IC2-PC2(ADC2))") (class "Default")
      (node (ref "IC2") (pin "25") (pinfunction "PC2(ADC2)_25") (pintype "bidirectional"))
      (node (ref "R34") (pin "2") (pinfunction "2_2") (pintype "passive"))
    )
    (net (code "68") (name "Net-(IC2-PC3(ADC3))") (class "Default")
      (node (ref "IC2") (pin "26") (pinfunction "PC3(ADC3)_26") (pintype "bidirectional"))
      (node (ref "R33") (pin "2") (pinfunction "2_2") (pintype "passive"))
    )
    (net (code "69") (name "Net-(IC2-PC4(ADC4{slash}SDA))") (class "Default")
      (node (ref "IC2") (pin "27") (pinfunction "PC4(ADC4/SDA)_27") (pintype "bidirectional"))
      (node (ref "R5") (pin "2") (pinfunction "2_2") (pintype "passive"))
    )
    (net (code "70") (name "Net-(IC2-PC5(ADC5{slash}SCL))") (class "Default")
      (node (ref "IC2") (pin "28") (pinfunction "PC5(ADC5/SCL)_28") (pintype "bidirectional"))
      (node (ref "R6") (pin "2") (pinfunction "2_2") (pintype "passive"))
    )
    (net (code "71") (name "Net-(IC2-PC6({slash}RESET))") (class "Default")
      (node (ref "IC2") (pin "1") (pinfunction "PC6(/RESET)_1") (pintype "bidirectional"))
      (node (ref "R1") (pin "1") (pinfunction "1_1") (pintype "passive"))
    )
    (net (code "72") (name "Net-(IC4-VI)") (class "Default")
      (node (ref "C5") (pin "+") (pinfunction "+_+") (pintype "passive"))
      (node (ref "IC4") (pin "1") (pinfunction "VI_1") (pintype "input"))
      (node (ref "Q4") (pin "3") (pinfunction "D_3") (pintype "passive"))
    )
    (net (code "73") (name "Net-(OK1-C)") (class "Default")
      (node (ref "OK1") (pin "2") (pinfunction "C_2") (pintype "passive"))
      (node (ref "R27") (pin "2") (pinfunction "2_2") (pintype "passive"))
    )
    (net (code "74") (name "Net-(OK1-EMIT)") (class "Default")
      (node (ref "OK1") (pin "3") (pinfunction "EMIT_3") (pintype "passive"))
      (node (ref "R3") (pin "1") (pinfunction "1_1") (pintype "passive"))
    )
    (net (code "75") (name "Net-(Q4-G)") (class "Default")
      (node (ref "C14") (pin "1") (pinfunction "1_1") (pintype "passive"))
      (node (ref "Q4") (pin "1") (pinfunction "G_1") (pintype "passive"))
      (node (ref "R28") (pin "1") (pinfunction "1_1") (pintype "passive"))
      (node (ref "T3") (pin "3") (pinfunction "C_3") (pintype "passive"))
    )
    (net (code "76") (name "Net-(T1-B)") (class "Default")
      (node (ref "R13") (pin "1") (pinfunction "1_1") (pintype "passive"))
      (node (ref "T1") (pin "2") (pinfunction "B_2") (pintype "passive"))
    )
    (net (code "77") (name "Net-(T2-B)") (class "Default")
      (node (ref "R18") (pin "2") (pinfunction "2_2") (pintype "passive"))
      (node (ref "T2") (pin "2") (pinfunction "B_2") (pintype "passive"))
    )
    (net (code "78") (name "Net-(T3-B)") (class "Default")
      (node (ref "R31") (pin "1") (pinfunction "1_1") (pintype "passive"))
      (node (ref "R35") (pin "1") (pinfunction "1_1") (pintype "passive"))
      (node (ref "T3") (pin "2") (pinfunction "B_2") (pintype "passive"))
    )
    (net (code "79") (name "POW_LATCH") (class "Default")
      (node (ref "D5") (pin "A") (pinfunction "A_A") (pintype "passive"))
      (node (ref "IC2") (pin "23") (pinfunction "PC0(ADC0)_23") (pintype "bidirectional"))
    )
    (net (code "80") (name "POW_OFF") (class "Default")
      (node (ref "CONN17") (pin "3") (pinfunction "3_3") (pintype "passive"))
      (node (ref "IC2") (pin "24") (pinfunction "PC1(ADC1)_24") (pintype "bidirectional"))
      (node (ref "R32") (pin "1") (pinfunction "1_1") (pintype "passive"))
    )
    (net (code "81") (name "ROW1") (class "Default")
      (node (ref "D2") (pin "C") (pinfunction "C_C") (pintype "passive"))
      (node (ref "D3") (pin "C") (pinfunction "C_C") (pintype "passive"))
      (node (ref "D4") (pin "C") (pinfunction "C_C") (pintype "passive"))
      (node (ref "IC1") (pin "4") (pinfunction "PD2(INT0)_4") (pintype "bidirectional"))
      (node (ref "R25") (pin "2") (pinfunction "2_2") (pintype "passive"))
    )
    (net (code "82") (name "ROW2") (class "Default")
      (node (ref "CONN8") (pin "P2") (pinfunction "2_P2") (pintype "bidirectional"))
      (node (ref "IC1") (pin "18") (pinfunction "PB4(MISO)_18") (pintype "bidirectional"))
      (node (ref "R26") (pin "2") (pinfunction "2_2") (pintype "passive"))
    )
    (net (code "83") (name "unconnected-(CONN3-3-PadP3)") (class "Default")
      (node (ref "CONN3") (pin "P3") (pinfunction "3_P3") (pintype "bidirectional"))
    )
    (net (code "84") (name "unconnected-(CONN4-3-PadP3)") (class "Default")
      (node (ref "CONN4") (pin "P3") (pinfunction "3_P3") (pintype "bidirectional"))
    )
    (net (code "85") (name "unconnected-(CONN5-2-PadP2)") (class "Default")
      (node (ref "CONN5") (pin "P2") (pinfunction "2_P2") (pintype "bidirectional"))
    )
    (net (code "86") (name "unconnected-(CONN5-4-PadP4)") (class "Default")
      (node (ref "CONN5") (pin "P4") (pinfunction "4_P4") (pintype "bidirectional"))
    )
    (net (code "87") (name "unconnected-(CONN8-1-PadP1)") (class "Default")
      (node (ref "CONN8") (pin "P1") (pinfunction "1_P1") (pintype "bidirectional"))
    )
    (net (code "88") (name "unconnected-(CONN16-1-PadP1)") (class "Default")
      (node (ref "CONN16") (pin "P1") (pinfunction "1_P1") (pintype "bidirectional"))
    )
    (net (code "89") (name "unconnected-(IC1-AREF-Pad21)") (class "Default")
      (node (ref "IC1") (pin "21") (pinfunction "AREF_21") (pintype "passive"))
    )
    (net (code "90") (name "unconnected-(IC2-AREF-Pad21)") (class "Default")
      (node (ref "IC2") (pin "21") (pinfunction "AREF_21") (pintype "passive"))
    )
    (net (code "91") (name "unconnected-(IC2-PD2(INT0)-Pad4)") (class "Default")
      (node (ref "IC2") (pin "4") (pinfunction "PD2(INT0)_4") (pintype "bidirectional"))
    )
    (net (code "92") (name "unconnected-(IC2-PD3(INT1)-Pad5)") (class "Default")
      (node (ref "IC2") (pin "5") (pinfunction "PD3(INT1)_5") (pintype "bidirectional"))
    )
    (net (code "93") (name "unconnected-(IC2-PD4(XCK{slash}T0)-Pad6)") (class "Default")
      (node (ref "IC2") (pin "6") (pinfunction "PD4(XCK/T0)_6") (pintype "bidirectional"))
    )
    (net (code "94") (name "unconnected-(IC2-PD5(T1)-Pad11)") (class "Default")
      (node (ref "IC2") (pin "11") (pinfunction "PD5(T1)_11") (pintype "bidirectional"))
    )
    (net (code "95") (name "unconnected-(IC2-PD7(AIN1)-Pad13)") (class "Default")
      (node (ref "IC2") (pin "13") (pinfunction "PD7(AIN1)_13") (pintype "bidirectional"))
    )
    (net (code "96") (name "unconnected-(IC3-QH*-Pad9)") (class "Default")
      (node (ref "IC3") (pin "9") (pinfunction "QH*_9") (pintype "tri_state"))
    )
  )
)
